# dog_treat_launcher.net
KiCad netlist of a schematic drawn in EAGLE
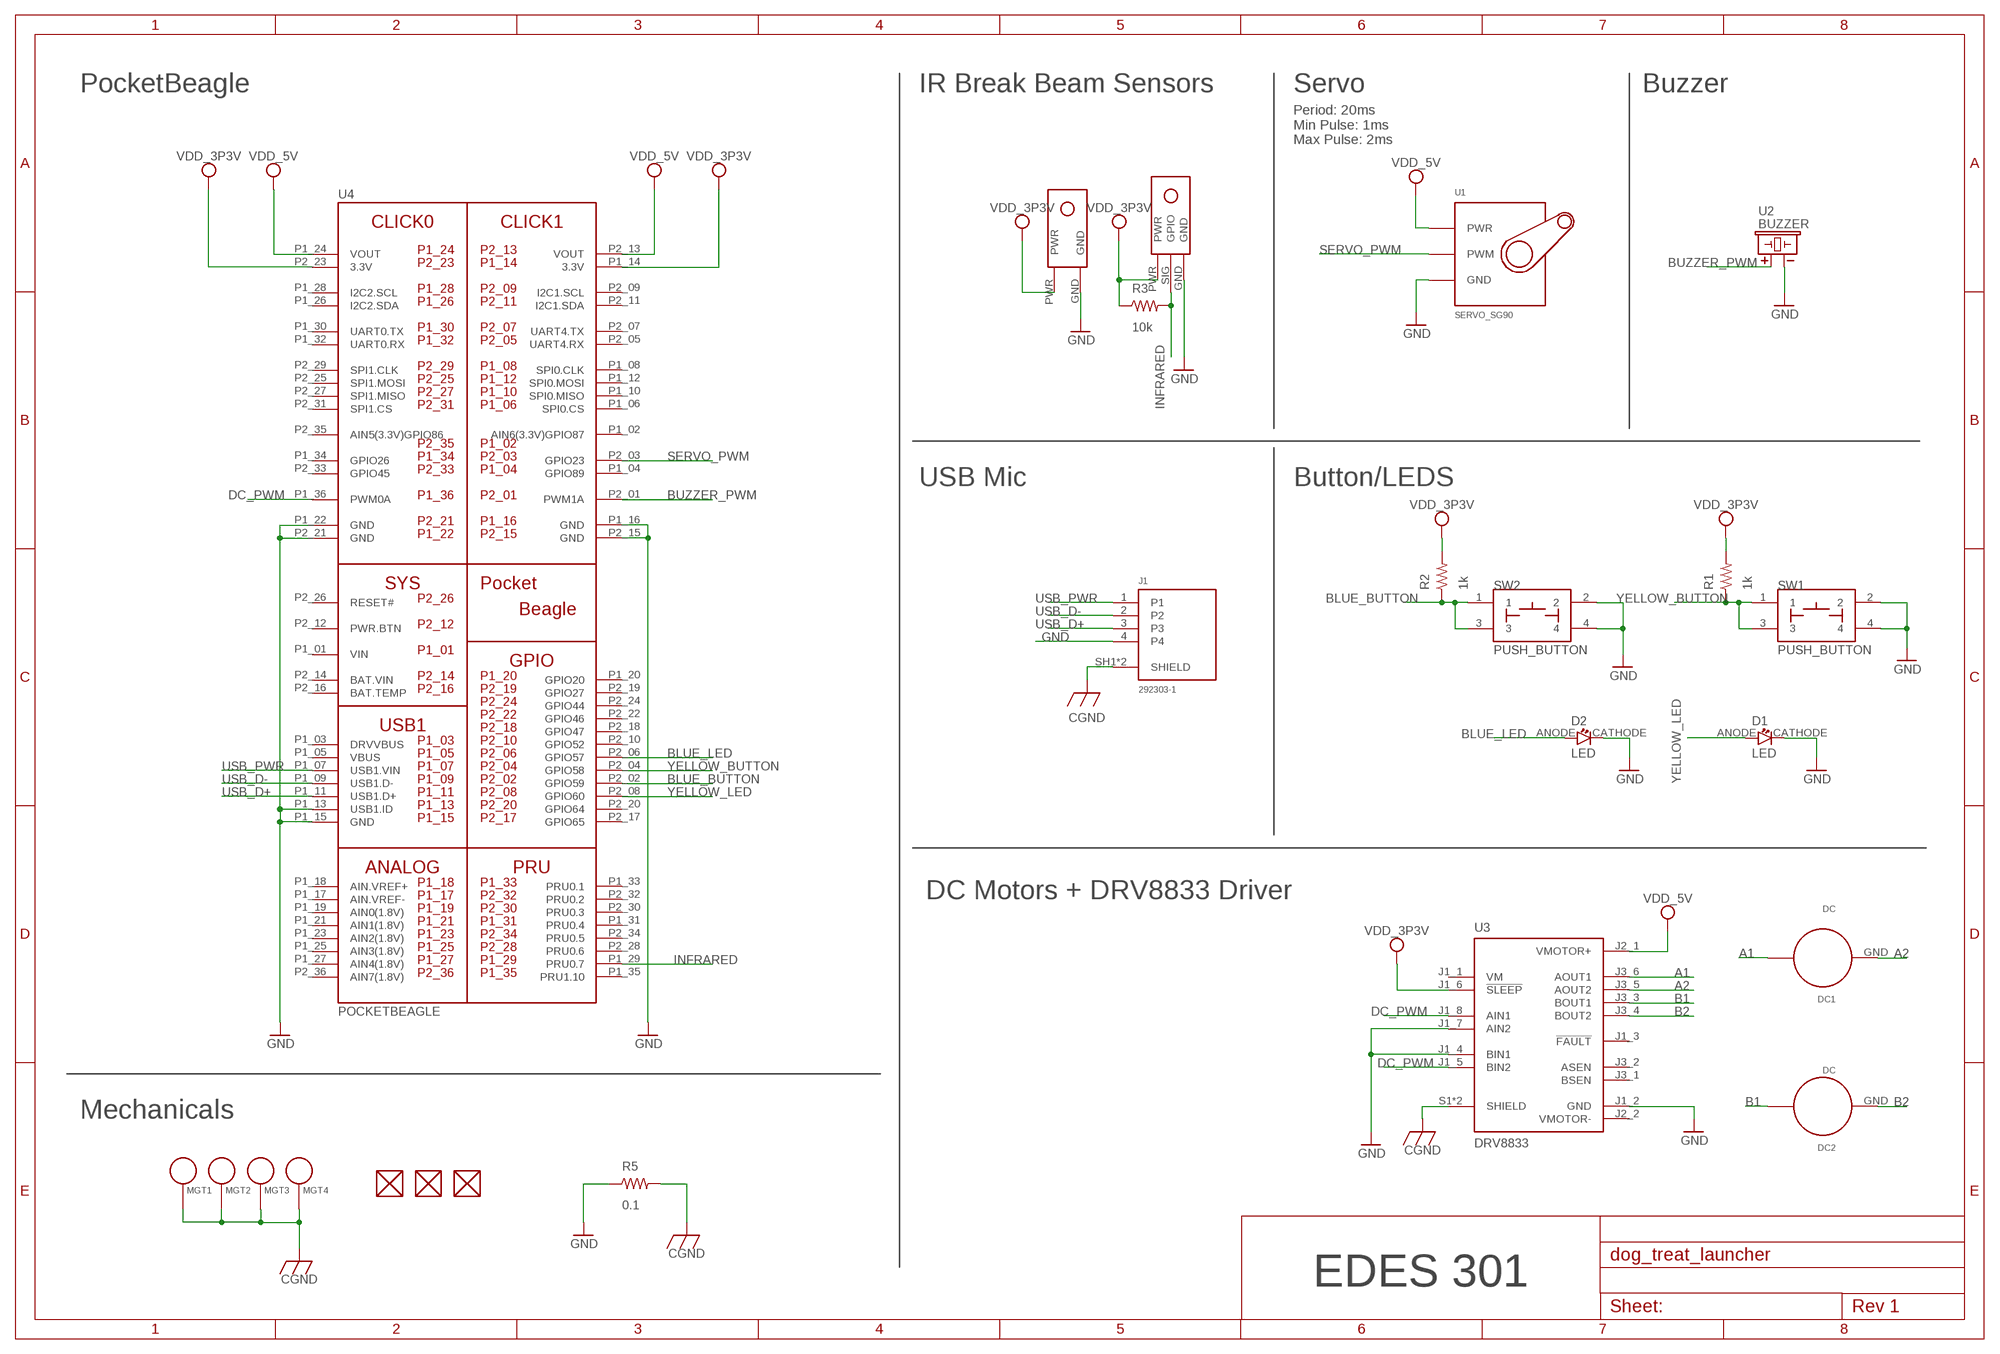
[diagram p0: schematic, sheet 1]

(export (version "E")
  (design (tool "Eeschema 10.0.6"))
  (components
    (comp (ref "D1")
      (value "LED")
      (footprint "eagle-import:EIA-STD")
      (libsource (lib "eagle-import") (part "LED"))
    )
    (comp (ref "D2")
      (value "LED")
      (footprint "eagle-import:EIA-STD")
      (libsource (lib "eagle-import") (part "LED"))
    )
    (comp (ref "DC1")
      (value "DC")
      (footprint "eagle-import:DC_FOOTPRINT")
      (libsource (lib "eagle-import") (part "DC"))
    )
    (comp (ref "DC2")
      (value "DC")
      (footprint "eagle-import:DC_FOOTPRINT")
      (libsource (lib "eagle-import") (part "DC"))
    )
    (comp (ref "FUD1")
      (value "FIDUCIAL")
      (footprint "eagle-import:FIDUCIAL_40MIL")
      (libsource (lib "eagle-import") (part "FIDUCIAL"))
    )
    (comp (ref "FUD2")
      (value "FIDUCIAL")
      (footprint "eagle-import:FIDUCIAL_40MIL")
      (libsource (lib "eagle-import") (part "FIDUCIAL"))
    )
    (comp (ref "FUD3")
      (value "FIDUCIAL")
      (footprint "eagle-import:FIDUCIAL_40MIL")
      (libsource (lib "eagle-import") (part "FIDUCIAL"))
    )
    (comp (ref "IR_T1")
      (value "IR_TRANSMITTER")
      (footprint "eagle-import:IR_T")
      (libsource (lib "eagle-import") (part "IR_TRANSMITTER"))
    )
    (comp (ref "IT_R1")
      (value "IR_RECIEVER")
      (footprint "eagle-import:IR_R")
      (libsource (lib "eagle-import") (part "IR_RECIEVER"))
    )
    (comp (ref "J1")
      (value "292303-1")
      (footprint "eagle-import:TE_292303-1")
      (fields (field (name "MF") "TE Connectivity"))
      (libsource (lib "eagle-import") (part "292303-1"))
    )
    (comp (ref "MGT1")
      (value "MOUNTING_HOLE")
      (footprint "eagle-import:MOUNTING_HOLE")
      (libsource (lib "eagle-import") (part "MOUNTING_HOLE"))
    )
    (comp (ref "MGT2")
      (value "MOUNTING_HOLE")
      (footprint "eagle-import:MOUNTING_HOLE")
      (libsource (lib "eagle-import") (part "MOUNTING_HOLE"))
    )
    (comp (ref "MGT3")
      (value "MOUNTING_HOLE")
      (footprint "eagle-import:MOUNTING_HOLE")
      (libsource (lib "eagle-import") (part "MOUNTING_HOLE"))
    )
    (comp (ref "MGT4")
      (value "MOUNTING_HOLE")
      (footprint "eagle-import:MOUNTING_HOLE")
      (libsource (lib "eagle-import") (part "MOUNTING_HOLE"))
    )
    (comp (ref "R1")
      (value "1k")
      (footprint "eagle-import:R0402")
      (libsource (lib "eagle-import") (part "R_R0402"))
    )
    (comp (ref "R2")
      (value "1k")
      (footprint "eagle-import:R0402")
      (libsource (lib "eagle-import") (part "R_R0402"))
    )
    (comp (ref "R3")
      (value "10k")
      (footprint "eagle-import:R0402")
      (libsource (lib "eagle-import") (part "R_R0402"))
    )
    (comp (ref "R5")
      (value "0.1")
      (footprint "eagle-import:R0402")
      (libsource (lib "eagle-import") (part "MISC_R_R0402"))
    )
    (comp (ref "SW1")
      (value "PUSH_BUTTON")
      (footprint "eagle-import:BUTTON_12.5MM")
      (libsource (lib "eagle-import") (part "PUSH_BUTTON"))
    )
    (comp (ref "SW2")
      (value "PUSH_BUTTON")
      (footprint "eagle-import:BUTTON_12.5MM")
      (libsource (lib "eagle-import") (part "PUSH_BUTTON"))
    )
    (comp (ref "U1")
      (value "SERVO_SG90")
      (footprint "eagle-import:SERVO-X1")
      (libsource (lib "eagle-import") (part "SERVO_SG90"))
    )
    (comp (ref "U2")
      (value "BUZZER")
      (footprint "eagle-import:BUZZER_6.5MM")
      (libsource (lib "eagle-import") (part "BUZZER"))
    )
    (comp (ref "U3")
      (value "DRV8833")
      (footprint "eagle-import:MODULE_3297")
      (fields (field (name "MF") "Adafruit Industries") (field (name "MP") "3297"))
      (libsource (lib "eagle-import") (part "DRV8833"))
    )
    (comp (ref "U4")
      (value "POCKETBEAGLE")
      (footprint "eagle-import:POCKETBEAGLE")
      (libsource (lib "eagle-import") (part "POCKETBEAGLE"))
    )
  )
  (nets
    (net (code "1") (name "/A1") (class "Default")
      (node (ref "DC1") (pin "PWR") (pinfunction "PWR_PWR") (pintype "power_in"))
      (node (ref "U3") (pin "J3_6") (pinfunction "AOUT1_J3_6") (pintype "output"))
    )
    (net (code "2") (name "/A2") (class "Default")
      (node (ref "DC1") (pin "GND") (pinfunction "GND_GND") (pintype "power_in"))
      (node (ref "U3") (pin "J3_5") (pinfunction "AOUT2_J3_5") (pintype "output"))
    )
    (net (code "3") (name "/B1") (class "Default")
      (node (ref "DC2") (pin "PWR") (pinfunction "PWR_PWR") (pintype "power_in"))
      (node (ref "U3") (pin "J3_3") (pinfunction "BOUT1_J3_3") (pintype "output"))
    )
    (net (code "4") (name "/B2") (class "Default")
      (node (ref "DC2") (pin "GND") (pinfunction "GND_GND") (pintype "power_in"))
      (node (ref "U3") (pin "J3_4") (pinfunction "BOUT2_J3_4") (pintype "output"))
    )
    (net (code "5") (name "/BAT.VIN") (class "Default")
      (node (ref "U4") (pin "P2_14") (pinfunction "BAT.VIN_P2_14") (pintype "power_in"))
    )
    (net (code "6") (name "/BLUE_BUTTON") (class "Default")
      (node (ref "R2") (pin "1") (pinfunction "1_1") (pintype "passive"))
      (node (ref "SW2") (pin "1") (pinfunction "1_1") (pintype "bidirectional"))
      (node (ref "SW2") (pin "3") (pinfunction "3_3") (pintype "bidirectional"))
      (node (ref "U4") (pin "P2_02") (pinfunction "GPIO59_P2_02") (pintype "bidirectional"))
    )
    (net (code "7") (name "/BLUE_LED") (class "Default")
      (node (ref "D2") (pin "ANODE") (pinfunction "ANODE_ANODE") (pintype "bidirectional"))
      (node (ref "U4") (pin "P2_06") (pinfunction "GPIO57_P2_06") (pintype "bidirectional"))
    )
    (net (code "8") (name "/BUZZER_PWM") (class "Default")
      (node (ref "U2") (pin "+") (pinfunction "+_+") (pintype "passive"))
      (node (ref "U4") (pin "P2_01") (pinfunction "PWM1A_P2_01") (pintype "bidirectional"))
    )
    (net (code "9") (name "/DC_PWM") (class "Default")
      (node (ref "U3") (pin "J1_5") (pinfunction "BIN2_J1_5") (pintype "input"))
      (node (ref "U3") (pin "J1_8") (pinfunction "AIN1_J1_8") (pintype "input"))
      (node (ref "U4") (pin "P1_36") (pinfunction "PWM0A_P1_36") (pintype "bidirectional"))
    )
    (net (code "10") (name "/INFRARED") (class "Default")
      (node (ref "IT_R1") (pin "SIG") (pinfunction "GPIO_SIG") (pintype "bidirectional"))
      (node (ref "R3") (pin "2") (pinfunction "2_2") (pintype "passive"))
      (node (ref "U4") (pin "P1_29") (pinfunction "PRU0.7_P1_29") (pintype "bidirectional"))
    )
    (net (code "11") (name "/SERVO_PWM") (class "Default")
      (node (ref "U1") (pin "SIG") (pinfunction "PWM_SIG") (pintype "bidirectional"))
      (node (ref "U4") (pin "P2_03") (pinfunction "GPIO23_P2_03") (pintype "bidirectional"))
    )
    (net (code "12") (name "/USB_D+") (class "Default")
      (node (ref "J1") (pin "3") (pinfunction "P3_3") (pintype "passive"))
      (node (ref "U4") (pin "P1_11") (pinfunction "USB1.D+_P1_11") (pintype "bidirectional"))
    )
    (net (code "13") (name "/USB_D-") (class "Default")
      (node (ref "J1") (pin "2") (pinfunction "P2_2") (pintype "passive"))
      (node (ref "U4") (pin "P1_09") (pinfunction "USB1.D-_P1_09") (pintype "bidirectional"))
    )
    (net (code "14") (name "/USB_PWR") (class "Default")
      (node (ref "J1") (pin "1") (pinfunction "P1_1") (pintype "passive"))
      (node (ref "U4") (pin "P1_07") (pinfunction "USB1.VIN_P1_07") (pintype "bidirectional"))
    )
    (net (code "15") (name "/VIN") (class "Default")
      (node (ref "U4") (pin "P1_01") (pinfunction "VIN_P1_01") (pintype "power_in"))
    )
    (net (code "16") (name "/VMOTOR-") (class "Default")
      (node (ref "U3") (pin "J2_2") (pinfunction "VMOTOR-_J2_2") (pintype "power_in"))
    )
    (net (code "17") (name "/YELLOW_BUTTON") (class "Default")
      (node (ref "R1") (pin "1") (pinfunction "1_1") (pintype "passive"))
      (node (ref "SW1") (pin "1") (pinfunction "1_1") (pintype "bidirectional"))
      (node (ref "SW1") (pin "3") (pinfunction "3_3") (pintype "bidirectional"))
      (node (ref "U4") (pin "P2_04") (pinfunction "GPIO58_P2_04") (pintype "bidirectional"))
    )
    (net (code "18") (name "/YELLOW_LED") (class "Default")
      (node (ref "D1") (pin "ANODE") (pinfunction "ANODE_ANODE") (pintype "bidirectional"))
      (node (ref "U4") (pin "P2_08") (pinfunction "GPIO60_P2_08") (pintype "bidirectional"))
    )
    (net (code "19") (name "CGND") (class "Default")
      (node (ref "J1") (pin "SH1") (pinfunction "SHIELD_SH1") (pintype "passive"))
      (node (ref "J1") (pin "SH2") (pinfunction "SHIELD_SH2") (pintype "passive"))
      (node (ref "MGT1") (pin "P$1") (pinfunction "P$1_P$1") (pintype "bidirectional"))
      (node (ref "MGT2") (pin "P$1") (pinfunction "P$1_P$1") (pintype "bidirectional"))
      (node (ref "MGT3") (pin "P$1") (pinfunction "P$1_P$1") (pintype "bidirectional"))
      (node (ref "MGT4") (pin "P$1") (pinfunction "P$1_P$1") (pintype "bidirectional"))
      (node (ref "R5") (pin "2") (pinfunction "2_2") (pintype "passive"))
      (node (ref "U3") (pin "S1") (pinfunction "SHIELD_S1") (pintype "passive"))
      (node (ref "U3") (pin "S2") (pinfunction "SHIELD_S2") (pintype "passive"))
    )
    (net (code "20") (name "GND") (class "Default")
      (node (ref "D1") (pin "CATHODE") (pinfunction "CATHODE_CATHODE") (pintype "bidirectional"))
      (node (ref "D2") (pin "CATHODE") (pinfunction "CATHODE_CATHODE") (pintype "bidirectional"))
      (node (ref "IR_T1") (pin "GND") (pinfunction "GND_GND") (pintype "bidirectional"))
      (node (ref "IT_R1") (pin "GND") (pinfunction "GND_GND") (pintype "bidirectional"))
      (node (ref "J1") (pin "4") (pinfunction "P4_4") (pintype "passive"))
      (node (ref "R5") (pin "1") (pinfunction "1_1") (pintype "passive"))
      (node (ref "SW1") (pin "2") (pinfunction "2_2") (pintype "bidirectional"))
      (node (ref "SW1") (pin "4") (pinfunction "4_4") (pintype "bidirectional"))
      (node (ref "SW2") (pin "2") (pinfunction "2_2") (pintype "bidirectional"))
      (node (ref "SW2") (pin "4") (pinfunction "4_4") (pintype "bidirectional"))
      (node (ref "U1") (pin "GND") (pinfunction "GND_GND") (pintype "bidirectional"))
      (node (ref "U2") (pin "-") (pinfunction "-_-") (pintype "passive"))
      (node (ref "U3") (pin "J1_2") (pinfunction "GND_J1_2") (pintype "power_in"))
      (node (ref "U3") (pin "J1_4") (pinfunction "BIN1_J1_4") (pintype "input"))
      (node (ref "U3") (pin "J1_7") (pinfunction "AIN2_J1_7") (pintype "input"))
      (node (ref "U4") (pin "P1_13") (pinfunction "USB1.ID_P1_13") (pintype "bidirectional"))
      (node (ref "U4") (pin "P1_15") (pinfunction "GND_P1_15") (pintype "bidirectional"))
      (node (ref "U4") (pin "P1_16") (pinfunction "GND_P1_16") (pintype "power_in"))
      (node (ref "U4") (pin "P1_22") (pinfunction "GND_P1_22") (pintype "power_in"))
      (node (ref "U4") (pin "P2_15") (pinfunction "GND_P2_15") (pintype "power_in"))
      (node (ref "U4") (pin "P2_21") (pinfunction "GND_P2_21") (pintype "power_in"))
    )
    (net (code "21") (name "VDD_3P3V") (class "Default")
      (node (ref "IR_T1") (pin "PWR") (pinfunction "PWR_PWR") (pintype "bidirectional"))
      (node (ref "IT_R1") (pin "PWR") (pinfunction "PWR_PWR") (pintype "bidirectional"))
      (node (ref "R1") (pin "2") (pinfunction "2_2") (pintype "passive"))
      (node (ref "R2") (pin "2") (pinfunction "2_2") (pintype "passive"))
      (node (ref "R3") (pin "1") (pinfunction "1_1") (pintype "passive"))
      (node (ref "U3") (pin "J1_6") (pinfunction "~{SLEEP}_J1_6") (pintype "input"))
      (node (ref "U4") (pin "P1_14") (pinfunction "3.3V_P1_14") (pintype "power_in"))
      (node (ref "U4") (pin "P2_23") (pinfunction "3.3V_P2_23") (pintype "power_in"))
    )
    (net (code "22") (name "VDD_5V") (class "Default")
      (node (ref "U1") (pin "PWR") (pinfunction "PWR_PWR") (pintype "bidirectional"))
      (node (ref "U3") (pin "J2_1") (pinfunction "VMOTOR+_J2_1") (pintype "power_in"))
      (node (ref "U4") (pin "P1_24") (pinfunction "VOUT_P1_24") (pintype "power_in"))
      (node (ref "U4") (pin "P2_13") (pinfunction "VOUT_P2_13") (pintype "power_in"))
    )
    (net (code "23") (name "unconnected-(FUD1-PadP$1)") (class "Default")
      (node (ref "FUD1") (pin "P$1") (pinfunction "P$1_P$1") (pintype "no_connect"))
    )
    (net (code "24") (name "unconnected-(FUD2-PadP$1)") (class "Default")
      (node (ref "FUD2") (pin "P$1") (pinfunction "P$1_P$1") (pintype "no_connect"))
    )
    (net (code "25") (name "unconnected-(FUD3-PadP$1)") (class "Default")
      (node (ref "FUD3") (pin "P$1") (pinfunction "P$1_P$1") (pintype "no_connect"))
    )
    (net (code "26") (name "unconnected-(U3-ASEN-PadJ3_2)") (class "Default")
      (node (ref "U3") (pin "J3_2") (pinfunction "ASEN_J3_2") (pintype "passive"))
    )
    (net (code "27") (name "unconnected-(U3-BSEN-PadJ3_1)") (class "Default")
      (node (ref "U3") (pin "J3_1") (pinfunction "BSEN_J3_1") (pintype "passive"))
    )
    (net (code "28") (name "unconnected-(U3-VM-PadJ1_1)") (class "Default")
      (node (ref "U3") (pin "J1_1") (pinfunction "VM_J1_1") (pintype "input"))
    )
    (net (code "29") (name "unconnected-(U3-~{FAULT}-PadJ1_3)") (class "Default")
      (node (ref "U3") (pin "J1_3") (pinfunction "~{FAULT}_J1_3") (pintype "output"))
    )
    (net (code "30") (name "unconnected-(U4-AIN.VREF+-PadP1_18)") (class "Default")
      (node (ref "U4") (pin "P1_18") (pinfunction "AIN.VREF+_P1_18") (pintype "input"))
    )
    (net (code "31") (name "unconnected-(U4-AIN.VREF--PadP1_17)") (class "Default")
      (node (ref "U4") (pin "P1_17") (pinfunction "AIN.VREF-_P1_17") (pintype "input"))
    )
    (net (code "32") (name "unconnected-(U4-AIN0(1.8V)-PadP1_19)") (class "Default")
      (node (ref "U4") (pin "P1_19") (pinfunction "AIN0(1.8V)_P1_19") (pintype "input"))
    )
    (net (code "33") (name "unconnected-(U4-AIN1(1.8V)-PadP1_21)") (class "Default")
      (node (ref "U4") (pin "P1_21") (pinfunction "AIN1(1.8V)_P1_21") (pintype "input"))
    )
    (net (code "34") (name "unconnected-(U4-AIN2(1.8V)-PadP1_23)") (class "Default")
      (node (ref "U4") (pin "P1_23") (pinfunction "AIN2(1.8V)_P1_23") (pintype "input"))
    )
    (net (code "35") (name "unconnected-(U4-AIN3(1.8V)-PadP1_25)") (class "Default")
      (node (ref "U4") (pin "P1_25") (pinfunction "AIN3(1.8V)_P1_25") (pintype "input"))
    )
    (net (code "36") (name "unconnected-(U4-AIN4(1.8V)-PadP1_27)") (class "Default")
      (node (ref "U4") (pin "P1_27") (pinfunction "AIN4(1.8V)_P1_27") (pintype "input"))
    )
    (net (code "37") (name "unconnected-(U4-AIN5(3.3V)GPIO86-PadP2_35)") (class "Default")
      (node (ref "U4") (pin "P2_35") (pinfunction "AIN5(3.3V)GPIO86_P2_35") (pintype "bidirectional"))
    )
    (net (code "38") (name "unconnected-(U4-AIN6(3.3V)GPIO87-PadP1_02)") (class "Default")
      (node (ref "U4") (pin "P1_02") (pinfunction "AIN6(3.3V)GPIO87_P1_02") (pintype "bidirectional"))
    )
    (net (code "39") (name "unconnected-(U4-AIN7(1.8V)-PadP2_36)") (class "Default")
      (node (ref "U4") (pin "P2_36") (pinfunction "AIN7(1.8V)_P2_36") (pintype "input"))
    )
    (net (code "40") (name "unconnected-(U4-BAT.TEMP-PadP2_16)") (class "Default")
      (node (ref "U4") (pin "P2_16") (pinfunction "BAT.TEMP_P2_16") (pintype "input"))
    )
    (net (code "41") (name "unconnected-(U4-DRVVBUS-PadP1_03)") (class "Default")
      (node (ref "U4") (pin "P1_03") (pinfunction "DRVVBUS_P1_03") (pintype "bidirectional"))
    )
    (net (code "42") (name "unconnected-(U4-GPIO20-PadP1_20)") (class "Default")
      (node (ref "U4") (pin "P1_20") (pinfunction "GPIO20_P1_20") (pintype "bidirectional"))
    )
    (net (code "43") (name "unconnected-(U4-GPIO26-PadP1_34)") (class "Default")
      (node (ref "U4") (pin "P1_34") (pinfunction "GPIO26_P1_34") (pintype "bidirectional"))
    )
    (net (code "44") (name "unconnected-(U4-GPIO27-PadP2_19)") (class "Default")
      (node (ref "U4") (pin "P2_19") (pinfunction "GPIO27_P2_19") (pintype "bidirectional"))
    )
    (net (code "45") (name "unconnected-(U4-GPIO44-PadP2_24)") (class "Default")
      (node (ref "U4") (pin "P2_24") (pinfunction "GPIO44_P2_24") (pintype "bidirectional"))
    )
    (net (code "46") (name "unconnected-(U4-GPIO45-PadP2_33)") (class "Default")
      (node (ref "U4") (pin "P2_33") (pinfunction "GPIO45_P2_33") (pintype "bidirectional"))
    )
    (net (code "47") (name "unconnected-(U4-GPIO46-PadP2_22)") (class "Default")
      (node (ref "U4") (pin "P2_22") (pinfunction "GPIO46_P2_22") (pintype "bidirectional"))
    )
    (net (code "48") (name "unconnected-(U4-GPIO47-PadP2_18)") (class "Default")
      (node (ref "U4") (pin "P2_18") (pinfunction "GPIO47_P2_18") (pintype "bidirectional"))
    )
    (net (code "49") (name "unconnected-(U4-GPIO52-PadP2_10)") (class "Default")
      (node (ref "U4") (pin "P2_10") (pinfunction "GPIO52_P2_10") (pintype "bidirectional"))
    )
    (net (code "50") (name "unconnected-(U4-GPIO64-PadP2_20)") (class "Default")
      (node (ref "U4") (pin "P2_20") (pinfunction "GPIO64_P2_20") (pintype "bidirectional"))
    )
    (net (code "51") (name "unconnected-(U4-GPIO65-PadP2_17)") (class "Default")
      (node (ref "U4") (pin "P2_17") (pinfunction "GPIO65_P2_17") (pintype "bidirectional"))
    )
    (net (code "52") (name "unconnected-(U4-GPIO89-PadP1_04)") (class "Default")
      (node (ref "U4") (pin "P1_04") (pinfunction "GPIO89_P1_04") (pintype "bidirectional"))
    )
    (net (code "53") (name "unconnected-(U4-I2C1.SCL-PadP2_09)") (class "Default")
      (node (ref "U4") (pin "P2_09") (pinfunction "I2C1.SCL_P2_09") (pintype "bidirectional"))
    )
    (net (code "54") (name "unconnected-(U4-I2C1.SDA-PadP2_11)") (class "Default")
      (node (ref "U4") (pin "P2_11") (pinfunction "I2C1.SDA_P2_11") (pintype "bidirectional"))
    )
    (net (code "55") (name "unconnected-(U4-I2C2.SCL-PadP1_28)") (class "Default")
      (node (ref "U4") (pin "P1_28") (pinfunction "I2C2.SCL_P1_28") (pintype "bidirectional"))
    )
    (net (code "56") (name "unconnected-(U4-I2C2.SDA-PadP1_26)") (class "Default")
      (node (ref "U4") (pin "P1_26") (pinfunction "I2C2.SDA_P1_26") (pintype "bidirectional"))
    )
    (net (code "57") (name "unconnected-(U4-PRU0.1-PadP1_33)") (class "Default")
      (node (ref "U4") (pin "P1_33") (pinfunction "PRU0.1_P1_33") (pintype "bidirectional"))
    )
    (net (code "58") (name "unconnected-(U4-PRU0.2-PadP2_32)") (class "Default")
      (node (ref "U4") (pin "P2_32") (pinfunction "PRU0.2_P2_32") (pintype "bidirectional"))
    )
    (net (code "59") (name "unconnected-(U4-PRU0.3-PadP2_30)") (class "Default")
      (node (ref "U4") (pin "P2_30") (pinfunction "PRU0.3_P2_30") (pintype "bidirectional"))
    )
    (net (code "60") (name "unconnected-(U4-PRU0.4-PadP1_31)") (class "Default")
      (node (ref "U4") (pin "P1_31") (pinfunction "PRU0.4_P1_31") (pintype "bidirectional"))
    )
    (net (code "61") (name "unconnected-(U4-PRU0.5-PadP2_34)") (class "Default")
      (node (ref "U4") (pin "P2_34") (pinfunction "PRU0.5_P2_34") (pintype "bidirectional"))
    )
    (net (code "62") (name "unconnected-(U4-PRU0.6-PadP2_28)") (class "Default")
      (node (ref "U4") (pin "P2_28") (pinfunction "PRU0.6_P2_28") (pintype "bidirectional"))
    )
    (net (code "63") (name "unconnected-(U4-PRU1.10-PadP1_35)") (class "Default")
      (node (ref "U4") (pin "P1_35") (pinfunction "PRU1.10_P1_35") (pintype "bidirectional"))
    )
    (net (code "64") (name "unconnected-(U4-PWR.BTN-PadP2_12)") (class "Default")
      (node (ref "U4") (pin "P2_12") (pinfunction "PWR.BTN_P2_12") (pintype "input"))
    )
    (net (code "65") (name "unconnected-(U4-RESET#-PadP2_26)") (class "Default")
      (node (ref "U4") (pin "P2_26") (pinfunction "RESET#_P2_26") (pintype "input"))
    )
    (net (code "66") (name "unconnected-(U4-SPI0.CLK-PadP1_08)") (class "Default")
      (node (ref "U4") (pin "P1_08") (pinfunction "SPI0.CLK_P1_08") (pintype "bidirectional"))
    )
    (net (code "67") (name "unconnected-(U4-SPI0.CS-PadP1_06)") (class "Default")
      (node (ref "U4") (pin "P1_06") (pinfunction "SPI0.CS_P1_06") (pintype "bidirectional"))
    )
    (net (code "68") (name "unconnected-(U4-SPI0.MISO-PadP1_10)") (class "Default")
      (node (ref "U4") (pin "P1_10") (pinfunction "SPI0.MISO_P1_10") (pintype "bidirectional"))
    )
    (net (code "69") (name "unconnected-(U4-SPI0.MOSI-PadP1_12)") (class "Default")
      (node (ref "U4") (pin "P1_12") (pinfunction "SPI0.MOSI_P1_12") (pintype "bidirectional"))
    )
    (net (code "70") (name "unconnected-(U4-SPI1.CLK-PadP2_29)") (class "Default")
      (node (ref "U4") (pin "P2_29") (pinfunction "SPI1.CLK_P2_29") (pintype "bidirectional"))
    )
    (net (code "71") (name "unconnected-(U4-SPI1.CS-PadP2_31)") (class "Default")
      (node (ref "U4") (pin "P2_31") (pinfunction "SPI1.CS_P2_31") (pintype "bidirectional"))
    )
    (net (code "72") (name "unconnected-(U4-SPI1.MISO-PadP2_27)") (class "Default")
      (node (ref "U4") (pin "P2_27") (pinfunction "SPI1.MISO_P2_27") (pintype "bidirectional"))
    )
    (net (code "73") (name "unconnected-(U4-SPI1.MOSI-PadP2_25)") (class "Default")
      (node (ref "U4") (pin "P2_25") (pinfunction "SPI1.MOSI_P2_25") (pintype "bidirectional"))
    )
    (net (code "74") (name "unconnected-(U4-UART0.RX-PadP1_32)") (class "Default")
      (node (ref "U4") (pin "P1_32") (pinfunction "UART0.RX_P1_32") (pintype "bidirectional"))
    )
    (net (code "75") (name "unconnected-(U4-UART0.TX-PadP1_30)") (class "Default")
      (node (ref "U4") (pin "P1_30") (pinfunction "UART0.TX_P1_30") (pintype "bidirectional"))
    )
    (net (code "76") (name "unconnected-(U4-UART4.RX-PadP2_05)") (class "Default")
      (node (ref "U4") (pin "P2_05") (pinfunction "UART4.RX_P2_05") (pintype "bidirectional"))
    )
    (net (code "77") (name "unconnected-(U4-UART4.TX-PadP2_07)") (class "Default")
      (node (ref "U4") (pin "P2_07") (pinfunction "UART4.TX_P2_07") (pintype "bidirectional"))
    )
    (net (code "78") (name "unconnected-(U4-VBUS-PadP1_05)") (class "Default")
      (node (ref "U4") (pin "P1_05") (pinfunction "VBUS_P1_05") (pintype "bidirectional"))
    )
  )
)
